# rbds_transmitter.net
KiCad netlist of a schematic drawn in EAGLE
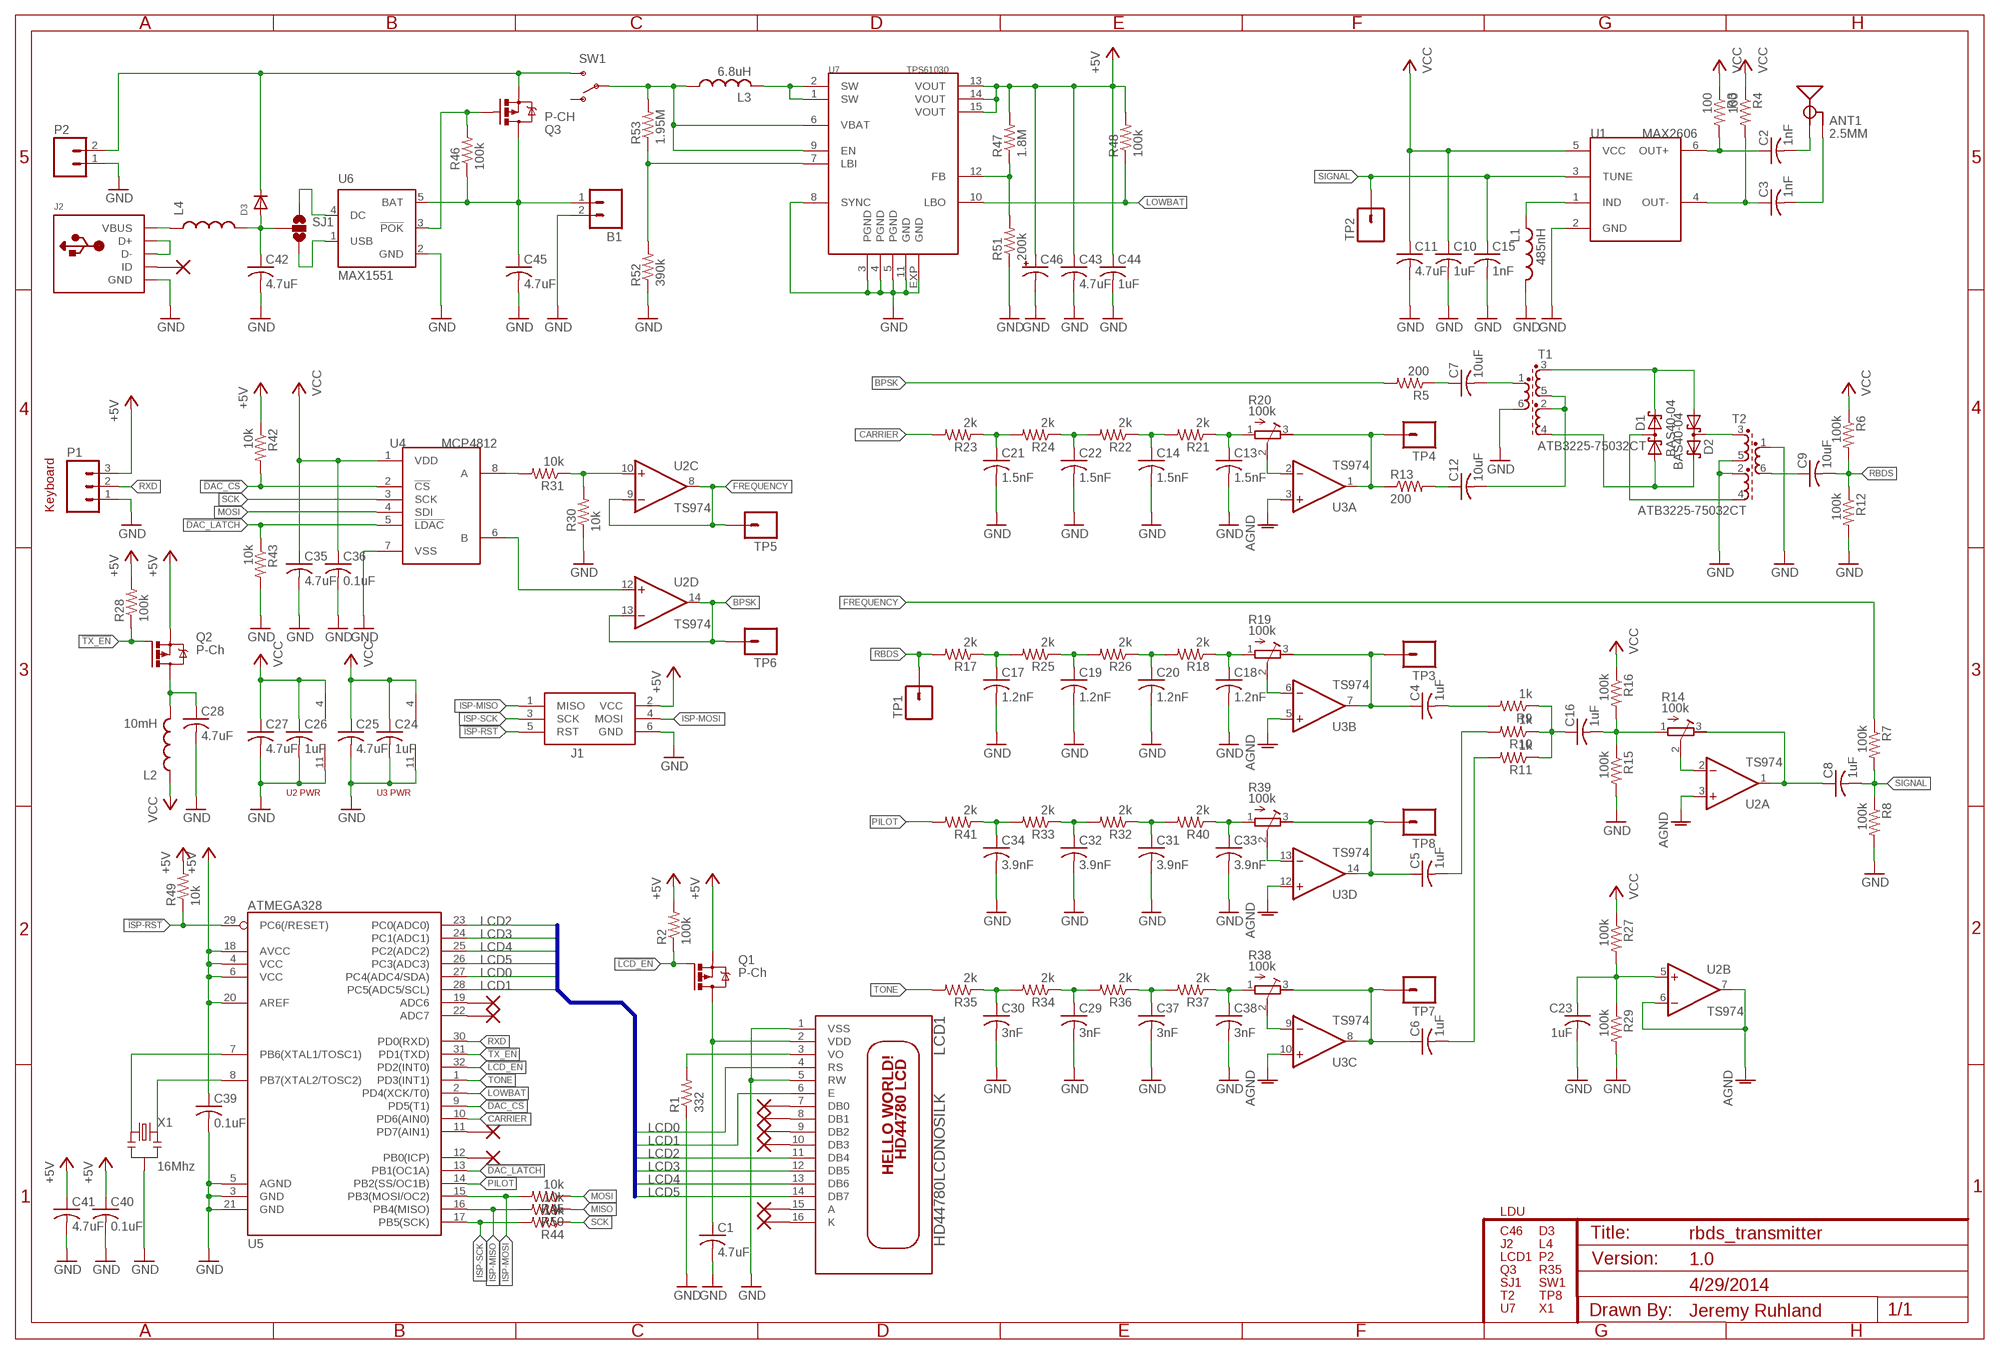
[diagram p0: schematic, sheet 1]

(export (version "E")
  (design (tool "Eeschema 10.0.6"))
  (components
    (comp (ref "ANT1")
      (value "2.5MM")
      (footprint "eagle-import:2.5MM_SCREW")
      (libsource (lib "eagle-import") (part "ANT2.5MM"))
    )
    (comp (ref "B1")
      (value "M02-JST-2MM-SMT")
      (footprint "eagle-import:JST-2-SMD")
      (libsource (lib "eagle-import") (part "M02-JST-2MM-SMT"))
    )
    (comp (ref "C1")
      (value "4.7uF")
      (footprint "eagle-import:C1206")
      (libsource (lib "eagle-import") (part "C-USC1206"))
    )
    (comp (ref "C2")
      (value "1nF")
      (footprint "eagle-import:C1206")
      (libsource (lib "eagle-import") (part "C-USC1206"))
    )
    (comp (ref "C3")
      (value "1nF")
      (footprint "eagle-import:C1206")
      (libsource (lib "eagle-import") (part "C-USC1206"))
    )
    (comp (ref "C4")
      (value "1uF")
      (footprint "eagle-import:C1206")
      (libsource (lib "eagle-import") (part "C-USC1206"))
    )
    (comp (ref "C5")
      (value "1uF")
      (footprint "eagle-import:C1206")
      (libsource (lib "eagle-import") (part "C-USC1206"))
    )
    (comp (ref "C6")
      (value "1uF")
      (footprint "eagle-import:C1206")
      (libsource (lib "eagle-import") (part "C-USC1206"))
    )
    (comp (ref "C7")
      (value "10uF")
      (footprint "eagle-import:C1206")
      (libsource (lib "eagle-import") (part "C-USC1206"))
    )
    (comp (ref "C8")
      (value "1uF")
      (footprint "eagle-import:C1206")
      (libsource (lib "eagle-import") (part "C-USC1206"))
    )
    (comp (ref "C9")
      (value "10uF")
      (footprint "eagle-import:C1206")
      (libsource (lib "eagle-import") (part "C-USC1206"))
    )
    (comp (ref "C10")
      (value "1uF")
      (footprint "eagle-import:C1206")
      (libsource (lib "eagle-import") (part "C-USC1206"))
    )
    (comp (ref "C11")
      (value "4.7uF")
      (footprint "eagle-import:C1206")
      (libsource (lib "eagle-import") (part "C-USC1206"))
    )
    (comp (ref "C12")
      (value "10uF")
      (footprint "eagle-import:C1206")
      (libsource (lib "eagle-import") (part "C-USC1206"))
    )
    (comp (ref "C13")
      (value "1.5nF")
      (footprint "eagle-import:C1206")
      (libsource (lib "eagle-import") (part "C-USC1206"))
    )
    (comp (ref "C14")
      (value "1.5nF")
      (footprint "eagle-import:C1206")
      (libsource (lib "eagle-import") (part "C-USC1206"))
    )
    (comp (ref "C15")
      (value "1nF")
      (footprint "eagle-import:C1206")
      (libsource (lib "eagle-import") (part "C-USC1206"))
    )
    (comp (ref "C16")
      (value "1uF")
      (footprint "eagle-import:C1206")
      (libsource (lib "eagle-import") (part "C-USC1206"))
    )
    (comp (ref "C17")
      (value "1.2nF")
      (footprint "eagle-import:C1206")
      (libsource (lib "eagle-import") (part "C-USC1206"))
    )
    (comp (ref "C18")
      (value "1.2nF")
      (footprint "eagle-import:C1206")
      (libsource (lib "eagle-import") (part "C-USC1206"))
    )
    (comp (ref "C19")
      (value "1.2nF")
      (footprint "eagle-import:C1206")
      (libsource (lib "eagle-import") (part "C-USC1206"))
    )
    (comp (ref "C20")
      (value "1.2nF")
      (footprint "eagle-import:C1206")
      (libsource (lib "eagle-import") (part "C-USC1206"))
    )
    (comp (ref "C21")
      (value "1.5nF")
      (footprint "eagle-import:C1206")
      (libsource (lib "eagle-import") (part "C-USC1206"))
    )
    (comp (ref "C22")
      (value "1.5nF")
      (footprint "eagle-import:C1206")
      (libsource (lib "eagle-import") (part "C-USC1206"))
    )
    (comp (ref "C23")
      (value "1uF")
      (footprint "eagle-import:C1206")
      (libsource (lib "eagle-import") (part "C-USC1206"))
    )
    (comp (ref "C24")
      (value "1uF")
      (footprint "eagle-import:C1206")
      (libsource (lib "eagle-import") (part "C-USC1206"))
    )
    (comp (ref "C25")
      (value "4.7uF")
      (footprint "eagle-import:C1206")
      (libsource (lib "eagle-import") (part "C-USC1206"))
    )
    (comp (ref "C26")
      (value "1uF")
      (footprint "eagle-import:C1206")
      (libsource (lib "eagle-import") (part "C-USC1206"))
    )
    (comp (ref "C27")
      (value "4.7uF")
      (footprint "eagle-import:C1206")
      (libsource (lib "eagle-import") (part "C-USC1206"))
    )
    (comp (ref "C28")
      (value "4.7uF")
      (footprint "eagle-import:C1206")
      (libsource (lib "eagle-import") (part "C-USC1206"))
    )
    (comp (ref "C29")
      (value "3nF")
      (footprint "eagle-import:C1206")
      (libsource (lib "eagle-import") (part "C-USC1206"))
    )
    (comp (ref "C30")
      (value "3nF")
      (footprint "eagle-import:C1206")
      (libsource (lib "eagle-import") (part "C-USC1206"))
    )
    (comp (ref "C31")
      (value "3.9nF")
      (footprint "eagle-import:C1206")
      (libsource (lib "eagle-import") (part "C-USC1206"))
    )
    (comp (ref "C32")
      (value "3.9nF")
      (footprint "eagle-import:C1206")
      (libsource (lib "eagle-import") (part "C-USC1206"))
    )
    (comp (ref "C33")
      (value "3.9nF")
      (footprint "eagle-import:C1206")
      (libsource (lib "eagle-import") (part "C-USC1206"))
    )
    (comp (ref "C34")
      (value "3.9nF")
      (footprint "eagle-import:C1206")
      (libsource (lib "eagle-import") (part "C-USC1206"))
    )
    (comp (ref "C35")
      (value "4.7uF")
      (footprint "eagle-import:C1206")
      (libsource (lib "eagle-import") (part "C-USC1206"))
    )
    (comp (ref "C36")
      (value "0.1uF")
      (footprint "eagle-import:C1206")
      (libsource (lib "eagle-import") (part "C-USC1206"))
    )
    (comp (ref "C37")
      (value "3nF")
      (footprint "eagle-import:C1206")
      (libsource (lib "eagle-import") (part "C-USC1206"))
    )
    (comp (ref "C38")
      (value "3nF")
      (footprint "eagle-import:C1206")
      (libsource (lib "eagle-import") (part "C-USC1206"))
    )
    (comp (ref "C39")
      (value "0.1uF")
      (footprint "eagle-import:C1206")
      (libsource (lib "eagle-import") (part "C-USC1206"))
    )
    (comp (ref "C40")
      (value "0.1uF")
      (footprint "eagle-import:C1206")
      (libsource (lib "eagle-import") (part "C-USC1206"))
    )
    (comp (ref "C41")
      (value "4.7uF")
      (footprint "eagle-import:C1206")
      (libsource (lib "eagle-import") (part "C-USC1206"))
    )
    (comp (ref "C42")
      (value "4.7uF")
      (footprint "eagle-import:C1206")
      (libsource (lib "eagle-import") (part "C-USC1206"))
    )
    (comp (ref "C43")
      (value "4.7uF")
      (footprint "eagle-import:C1206")
      (libsource (lib "eagle-import") (part "C-USC1206"))
    )
    (comp (ref "C44")
      (value "1uF")
      (footprint "eagle-import:C1206")
      (libsource (lib "eagle-import") (part "C-USC1206"))
    )
    (comp (ref "C45")
      (value "4.7uF")
      (footprint "eagle-import:C1206")
      (libsource (lib "eagle-import") (part "C-USC1206"))
    )
    (comp (ref "C46")
      (value "CPOL-USE")
      (footprint "eagle-import:PANASONIC_E")
      (libsource (lib "eagle-import") (part "CPOL-USE"))
    )
    (comp (ref "D1")
      (value "BAS40-04")
      (footprint "eagle-import:SOT23")
      (libsource (lib "eagle-import") (part "BAS40-04"))
    )
    (comp (ref "D2")
      (value "BAS40-04")
      (footprint "eagle-import:SOT23")
      (libsource (lib "eagle-import") (part "BAS40-04"))
    )
    (comp (ref "D3")
      (value "DIODESOD-123")
      (footprint "eagle-import:SOD-123")
      (libsource (lib "eagle-import") (part "DIODESOD-123"))
    )
    (comp (ref "J1")
      (value "AVRISP-6")
      (footprint "eagle-import:AVRISP")
      (libsource (lib "eagle-import") (part "AVRISP-6"))
    )
    (comp (ref "J2")
      (value "USBMINIB")
      (footprint "eagle-import:USB-MINIB")
      (libsource (lib "eagle-import") (part "USBMINIB"))
    )
    (comp (ref "L1")
      (value "485nH")
      (footprint "eagle-import:L3216C")
      (libsource (lib "eagle-import") (part "L-USL3216C"))
    )
    (comp (ref "L2")
      (value "10mH")
      (footprint "eagle-import:1210")
      (libsource (lib "eagle-import") (part "INDUCTOR1210"))
    )
    (comp (ref "L3")
      (value "6.8uH")
      (footprint "eagle-import:8040")
      (libsource (lib "eagle-import") (part "L"))
    )
    (comp (ref "L4")
      (value "INDUCTOR1210")
      (footprint "eagle-import:1210")
      (libsource (lib "eagle-import") (part "INDUCTOR1210"))
    )
    (comp (ref "LCD1")
      (value "HD44780LCDNOSILK")
      (footprint "eagle-import:LCD1602_NOSILK")
      (libsource (lib "eagle-import") (part "HD44780LCDNOSILK"))
    )
    (comp (ref "P1")
      (value "M03PTH")
      (footprint "eagle-import:1X03")
      (libsource (lib "eagle-import") (part "M03PTH"))
    )
    (comp (ref "P2")
      (value "M023.5MM")
      (footprint "eagle-import:SCREWTERMINAL-3.5MM-2")
      (libsource (lib "eagle-import") (part "M023.5MM"))
    )
    (comp (ref "Q1")
      (value "P-Ch")
      (footprint "eagle-import:MICRO3")
      (libsource (lib "eagle-import") (part "IRLML5203"))
    )
    (comp (ref "Q2")
      (value "P-Ch")
      (footprint "eagle-import:MICRO3")
      (libsource (lib "eagle-import") (part "IRLML5203"))
    )
    (comp (ref "Q3")
      (value "P-CH")
      (footprint "eagle-import:SOT23-3")
      (libsource (lib "eagle-import") (part "MOSFET-PCHANNELSMD"))
    )
    (comp (ref "R1")
      (value "332")
      (footprint "eagle-import:R1206")
      (libsource (lib "eagle-import") (part "R-US_R1206"))
    )
    (comp (ref "R2")
      (value "100k")
      (footprint "eagle-import:R1206")
      (libsource (lib "eagle-import") (part "R-US_R1206"))
    )
    (comp (ref "R3")
      (value "100")
      (footprint "eagle-import:R1206")
      (libsource (lib "eagle-import") (part "R-US_R1206"))
    )
    (comp (ref "R4")
      (value "100")
      (footprint "eagle-import:R1206")
      (libsource (lib "eagle-import") (part "R-US_R1206"))
    )
    (comp (ref "R5")
      (value "200")
      (footprint "eagle-import:R1206")
      (libsource (lib "eagle-import") (part "R-US_R1206"))
    )
    (comp (ref "R6")
      (value "100k")
      (footprint "eagle-import:R1206")
      (libsource (lib "eagle-import") (part "R-US_R1206"))
    )
    (comp (ref "R7")
      (value "100k")
      (footprint "eagle-import:R1206")
      (libsource (lib "eagle-import") (part "R-US_R1206"))
    )
    (comp (ref "R8")
      (value "100k")
      (footprint "eagle-import:R1206")
      (libsource (lib "eagle-import") (part "R-US_R1206"))
    )
    (comp (ref "R9")
      (value "1k")
      (footprint "eagle-import:R1206")
      (libsource (lib "eagle-import") (part "R-US_R1206"))
    )
    (comp (ref "R10")
      (value "1k")
      (footprint "eagle-import:R1206")
      (libsource (lib "eagle-import") (part "R-US_R1206"))
    )
    (comp (ref "R11")
      (value "1k")
      (footprint "eagle-import:R1206")
      (libsource (lib "eagle-import") (part "R-US_R1206"))
    )
    (comp (ref "R12")
      (value "100k")
      (footprint "eagle-import:R1206")
      (libsource (lib "eagle-import") (part "R-US_R1206"))
    )
    (comp (ref "R13")
      (value "200")
      (footprint "eagle-import:R1206")
      (libsource (lib "eagle-import") (part "R-US_R1206"))
    )
    (comp (ref "R14")
      (value "100k")
      (footprint "eagle-import:RTRIM3304W")
      (libsource (lib "eagle-import") (part "R-TRIMM3304W"))
    )
    (comp (ref "R15")
      (value "100k")
      (footprint "eagle-import:R1206")
      (libsource (lib "eagle-import") (part "R-US_R1206"))
    )
    (comp (ref "R16")
      (value "100k")
      (footprint "eagle-import:R1206")
      (libsource (lib "eagle-import") (part "R-US_R1206"))
    )
    (comp (ref "R17")
      (value "2k")
      (footprint "eagle-import:R1206")
      (libsource (lib "eagle-import") (part "R-US_R1206"))
    )
    (comp (ref "R18")
      (value "2k")
      (footprint "eagle-import:R1206")
      (libsource (lib "eagle-import") (part "R-US_R1206"))
    )
    (comp (ref "R19")
      (value "100k")
      (footprint "eagle-import:RTRIM3304W")
      (libsource (lib "eagle-import") (part "R-TRIMM3304W"))
    )
    (comp (ref "R20")
      (value "100k")
      (footprint "eagle-import:RTRIM3304W")
      (libsource (lib "eagle-import") (part "R-TRIMM3304W"))
    )
    (comp (ref "R21")
      (value "2k")
      (footprint "eagle-import:R1206")
      (libsource (lib "eagle-import") (part "R-US_R1206"))
    )
    (comp (ref "R22")
      (value "2k")
      (footprint "eagle-import:R1206")
      (libsource (lib "eagle-import") (part "R-US_R1206"))
    )
    (comp (ref "R23")
      (value "2k")
      (footprint "eagle-import:R1206")
      (libsource (lib "eagle-import") (part "R-US_R1206"))
    )
    (comp (ref "R24")
      (value "2k")
      (footprint "eagle-import:R1206")
      (libsource (lib "eagle-import") (part "R-US_R1206"))
    )
    (comp (ref "R25")
      (value "2k")
      (footprint "eagle-import:R1206")
      (libsource (lib "eagle-import") (part "R-US_R1206"))
    )
    (comp (ref "R26")
      (value "2k")
      (footprint "eagle-import:R1206")
      (libsource (lib "eagle-import") (part "R-US_R1206"))
    )
    (comp (ref "R27")
      (value "100k")
      (footprint "eagle-import:R1206")
      (libsource (lib "eagle-import") (part "R-US_R1206"))
    )
    (comp (ref "R28")
      (value "100k")
      (footprint "eagle-import:R1206")
      (libsource (lib "eagle-import") (part "R-US_R1206"))
    )
    (comp (ref "R29")
      (value "100k")
      (footprint "eagle-import:R1206")
      (libsource (lib "eagle-import") (part "R-US_R1206"))
    )
    (comp (ref "R30")
      (value "10k")
      (footprint "eagle-import:R1206")
      (libsource (lib "eagle-import") (part "R-US_R1206"))
    )
    (comp (ref "R31")
      (value "10k")
      (footprint "eagle-import:R1206")
      (libsource (lib "eagle-import") (part "R-US_R1206"))
    )
    (comp (ref "R32")
      (value "2k")
      (footprint "eagle-import:R1206")
      (libsource (lib "eagle-import") (part "R-US_R1206"))
    )
    (comp (ref "R33")
      (value "2k")
      (footprint "eagle-import:R1206")
      (libsource (lib "eagle-import") (part "R-US_R1206"))
    )
    (comp (ref "R34")
      (value "2k")
      (footprint "eagle-import:R1206")
      (libsource (lib "eagle-import") (part "R-US_R1206"))
    )
    (comp (ref "R35")
      (value "2k")
      (footprint "eagle-import:R1206")
      (libsource (lib "eagle-import") (part "R-US_R1206"))
    )
    (comp (ref "R36")
      (value "2k")
      (footprint "eagle-import:R1206")
      (libsource (lib "eagle-import") (part "R-US_R1206"))
    )
    (comp (ref "R37")
      (value "2k")
      (footprint "eagle-import:R1206")
      (libsource (lib "eagle-import") (part "R-US_R1206"))
    )
    (comp (ref "R38")
      (value "100k")
      (footprint "eagle-import:RTRIM3304W")
      (libsource (lib "eagle-import") (part "R-TRIMM3304W"))
    )
    (comp (ref "R39")
      (value "100k")
      (footprint "eagle-import:RTRIM3304W")
      (libsource (lib "eagle-import") (part "R-TRIMM3304W"))
    )
    (comp (ref "R40")
      (value "2k")
      (footprint "eagle-import:R1206")
      (libsource (lib "eagle-import") (part "R-US_R1206"))
    )
    (comp (ref "R41")
      (value "2k")
      (footprint "eagle-import:R1206")
      (libsource (lib "eagle-import") (part "R-US_R1206"))
    )
    (comp (ref "R42")
      (value "10k")
      (footprint "eagle-import:R1206")
      (libsource (lib "eagle-import") (part "R-US_R1206"))
    )
    (comp (ref "R43")
      (value "10k")
      (footprint "eagle-import:R1206")
      (libsource (lib "eagle-import") (part "R-US_R1206"))
    )
    (comp (ref "R44")
      (value "10k")
      (footprint "eagle-import:R1206")
      (libsource (lib "eagle-import") (part "R-US_R1206"))
    )
    (comp (ref "R45")
      (value "10k")
      (footprint "eagle-import:R1206")
      (libsource (lib "eagle-import") (part "R-US_R1206"))
    )
    (comp (ref "R46")
      (value "100k")
      (footprint "eagle-import:R1206")
      (libsource (lib "eagle-import") (part "R-US_R1206"))
    )
    (comp (ref "R47")
      (value "1.8M")
      (footprint "eagle-import:R1206")
      (libsource (lib "eagle-import") (part "R-US_R1206"))
    )
    (comp (ref "R48")
      (value "100k")
      (footprint "eagle-import:R1206")
      (libsource (lib "eagle-import") (part "R-US_R1206"))
    )
    (comp (ref "R49")
      (value "10k")
      (footprint "eagle-import:R1206")
      (libsource (lib "eagle-import") (part "R-US_R1206"))
    )
    (comp (ref "R50")
      (value "10k")
      (footprint "eagle-import:R1206")
      (libsource (lib "eagle-import") (part "R-US_R1206"))
    )
    (comp (ref "R51")
      (value "200k")
      (footprint "eagle-import:R1206")
      (libsource (lib "eagle-import") (part "R-US_R1206"))
    )
    (comp (ref "R52")
      (value "390k")
      (footprint "eagle-import:R1206")
      (libsource (lib "eagle-import") (part "R-US_R1206"))
    )
    (comp (ref "R53")
      (value "1.95M")
      (footprint "eagle-import:R1206")
      (libsource (lib "eagle-import") (part "R-US_R1206"))
    )
    (comp (ref "SJ1")
      (value "SOLDERJUMPER_2WAYS")
      (footprint "eagle-import:SJ_3")
      (libsource (lib "eagle-import") (part "SOLDERJUMPER_2WAYS"))
    )
    (comp (ref "SW1")
      (value "SWITCH-SPSTSMD2")
      (footprint "eagle-import:SWITCH-SPDT-SMD")
      (libsource (lib "eagle-import") (part "SWITCH-SPSTSMD2"))
    )
    (comp (ref "T1")
      (value "ATB3225-75032CT")
      (footprint "eagle-import:TRANS")
      (libsource (lib "eagle-import") (part "ATB3225-75032CT"))
    )
    (comp (ref "T2")
      (value "ATB3225-75032CT")
      (footprint "eagle-import:TRANS")
      (libsource (lib "eagle-import") (part "ATB3225-75032CT"))
    )
    (comp (ref "TP1")
      (value "M01PTH")
      (footprint "eagle-import:1X01")
      (libsource (lib "eagle-import") (part "M01PTH"))
    )
    (comp (ref "TP2")
      (value "M01PTH")
      (footprint "eagle-import:1X01")
      (libsource (lib "eagle-import") (part "M01PTH"))
    )
    (comp (ref "TP3")
      (value "M01PTH")
      (footprint "eagle-import:1X01")
      (libsource (lib "eagle-import") (part "M01PTH"))
    )
    (comp (ref "TP4")
      (value "M01PTH")
      (footprint "eagle-import:1X01")
      (libsource (lib "eagle-import") (part "M01PTH"))
    )
    (comp (ref "TP5")
      (value "M01PTH")
      (footprint "eagle-import:1X01")
      (libsource (lib "eagle-import") (part "M01PTH"))
    )
    (comp (ref "TP6")
      (value "M01PTH")
      (footprint "eagle-import:1X01")
      (libsource (lib "eagle-import") (part "M01PTH"))
    )
    (comp (ref "TP7")
      (value "M01PTH")
      (footprint "eagle-import:1X01")
      (libsource (lib "eagle-import") (part "M01PTH"))
    )
    (comp (ref "TP8")
      (value "M01PTH")
      (footprint "eagle-import:1X01")
      (libsource (lib "eagle-import") (part "M01PTH"))
    )
    (comp (ref "U1")
      (value "MAX2606")
      (footprint "eagle-import:SOT23-6L")
      (libsource (lib "eagle-import") (part "MAX2606"))
    )
    (comp (ref "U2")
      (value "TS974")
      (footprint "eagle-import:SO14")
      (libsource (lib "eagle-import") (part "OPA4743UA"))
    )
    (comp (ref "U3")
      (value "TS974")
      (footprint "eagle-import:SO14")
      (libsource (lib "eagle-import") (part "OPA4743UA"))
    )
    (comp (ref "U4")
      (value "MCP4812")
      (footprint "eagle-import:SO-08")
      (libsource (lib "eagle-import") (part "MCP4812"))
    )
    (comp (ref "U5")
      (value "ATMEGA328")
      (footprint "eagle-import:TQFP32-08")
      (libsource (lib "eagle-import") (part "ATMEGA168"))
    )
    (comp (ref "U6")
      (value "MAX1551")
      (footprint "eagle-import:SOT23-5L")
      (fields (field (name "MF") "MAXIM") (field (name "MPN") "MAX1551EZK-T"))
      (libsource (lib "eagle-import") (part "MAX1551"))
    )
    (comp (ref "U7")
      (value "TPS61030")
      (footprint "eagle-import:HTSSOP16")
      (libsource (lib "eagle-import") (part "TPS61030"))
    )
    (comp (ref "X1")
      (value "16Mhz")
      (footprint "eagle-import:RESONATOR-SMD")
      (libsource (lib "eagle-import") (part "RESONATORSMD"))
    )
  )
  (nets
    (net (code "1") (name "+5V") (class "Default")
      (node (ref "C39") (pin "1") (pinfunction "1_1") (pintype "passive"))
      (node (ref "C40") (pin "1") (pinfunction "1_1") (pintype "passive"))
      (node (ref "C41") (pin "1") (pinfunction "1_1") (pintype "passive"))
      (node (ref "C43") (pin "1") (pinfunction "1_1") (pintype "passive"))
      (node (ref "C44") (pin "1") (pinfunction "1_1") (pintype "passive"))
      (node (ref "C46") (pin "+") (pinfunction "+_+") (pintype "passive"))
      (node (ref "J1") (pin "2") (pinfunction "VCC_2") (pintype "power_in"))
      (node (ref "P1") (pin "3") (pinfunction "3_3") (pintype "passive"))
      (node (ref "Q1") (pin "2") (pinfunction "S_2") (pintype "passive"))
      (node (ref "Q2") (pin "2") (pinfunction "S_2") (pintype "passive"))
      (node (ref "R2") (pin "2") (pinfunction "2_2") (pintype "passive"))
      (node (ref "R28") (pin "2") (pinfunction "2_2") (pintype "passive"))
      (node (ref "R42") (pin "1") (pinfunction "1_1") (pintype "passive"))
      (node (ref "R47") (pin "2") (pinfunction "2_2") (pintype "passive"))
      (node (ref "R48") (pin "2") (pinfunction "2_2") (pintype "passive"))
      (node (ref "R49") (pin "2") (pinfunction "2_2") (pintype "passive"))
      (node (ref "U5") (pin "18") (pinfunction "AVCC_18") (pintype "bidirectional"))
      (node (ref "U5") (pin "20") (pinfunction "AREF_20") (pintype "bidirectional"))
      (node (ref "U5") (pin "4") (pinfunction "VCC_4") (pintype "bidirectional"))
      (node (ref "U5") (pin "6") (pinfunction "VCC_6") (pintype "bidirectional"))
      (node (ref "U7") (pin "13") (pinfunction "VOUT_13") (pintype "bidirectional"))
      (node (ref "U7") (pin "14") (pinfunction "VOUT_14") (pintype "bidirectional"))
      (node (ref "U7") (pin "15") (pinfunction "VOUT_15") (pintype "bidirectional"))
    )
    (net (code "2") (name "/LCD0") (class "Default")
      (node (ref "LCD1") (pin "4") (pinfunction "RS_4") (pintype "input"))
      (node (ref "U5") (pin "27") (pinfunction "PC4(ADC4/SDA)_27") (pintype "bidirectional"))
    )
    (net (code "3") (name "/LCD1") (class "Default")
      (node (ref "LCD1") (pin "6") (pinfunction "E_6") (pintype "input"))
      (node (ref "U5") (pin "28") (pinfunction "PC5(ADC5/SCL)_28") (pintype "bidirectional"))
    )
    (net (code "4") (name "/LCD2") (class "Default")
      (node (ref "LCD1") (pin "11") (pinfunction "DB4_11") (pintype "bidirectional"))
      (node (ref "U5") (pin "23") (pinfunction "PC0(ADC0)_23") (pintype "bidirectional"))
    )
    (net (code "5") (name "/LCD3") (class "Default")
      (node (ref "LCD1") (pin "12") (pinfunction "DB5_12") (pintype "bidirectional"))
      (node (ref "U5") (pin "24") (pinfunction "PC1(ADC1)_24") (pintype "bidirectional"))
    )
    (net (code "6") (name "/LCD4") (class "Default")
      (node (ref "LCD1") (pin "13") (pinfunction "DB6_13") (pintype "bidirectional"))
      (node (ref "U5") (pin "25") (pinfunction "PC2(ADC2)_25") (pintype "bidirectional"))
    )
    (net (code "7") (name "/LCD5") (class "Default")
      (node (ref "LCD1") (pin "14") (pinfunction "DB7_14") (pintype "bidirectional"))
      (node (ref "U5") (pin "26") (pinfunction "PC3(ADC3)_26") (pintype "bidirectional"))
    )
    (net (code "8") (name "/~{DAC_CS}") (class "Default")
      (node (ref "R42") (pin "2") (pinfunction "2_2") (pintype "passive"))
      (node (ref "U4") (pin "2") (pinfunction "~{CS}_2") (pintype "bidirectional"))
      (node (ref "U5") (pin "9") (pinfunction "PD5(T1)_9") (pintype "bidirectional"))
    )
    (net (code "9") (name "/~{DAC_LATCH}") (class "Default")
      (node (ref "R43") (pin "1") (pinfunction "1_1") (pintype "passive"))
      (node (ref "U4") (pin "5") (pinfunction "~{LDAC}_5") (pintype "bidirectional"))
      (node (ref "U5") (pin "13") (pinfunction "PB1(OC1A)_13") (pintype "bidirectional"))
    )
    (net (code "10") (name "/~{ISP-RST}") (class "Default")
      (node (ref "J1") (pin "5") (pinfunction "RST_5") (pintype "output"))
      (node (ref "R49") (pin "1") (pinfunction "1_1") (pintype "passive"))
      (node (ref "U5") (pin "29") (pinfunction "PC6(/RESET)_29") (pintype "bidirectional"))
    )
    (net (code "11") (name "/~{LCD_EN}") (class "Default")
      (node (ref "Q1") (pin "1") (pinfunction "G_1") (pintype "passive"))
      (node (ref "R2") (pin "1") (pinfunction "1_1") (pintype "passive"))
      (node (ref "U5") (pin "32") (pinfunction "PD2(INT0)_32") (pintype "bidirectional"))
    )
    (net (code "12") (name "/~{TX_EN}") (class "Default")
      (node (ref "Q2") (pin "1") (pinfunction "G_1") (pintype "passive"))
      (node (ref "R28") (pin "1") (pinfunction "1_1") (pintype "passive"))
      (node (ref "U5") (pin "31") (pinfunction "PD1(TXD)_31") (pintype "bidirectional"))
    )
    (net (code "13") (name "AGND") (class "Default")
      (node (ref "U2") (pin "3") (pinfunction "+IN_3") (pintype "input"))
      (node (ref "U2") (pin "6") (pinfunction "-IN_6") (pintype "input"))
      (node (ref "U2") (pin "7") (pinfunction "OUT_7") (pintype "output"))
      (node (ref "U3") (pin "10") (pinfunction "+IN_10") (pintype "input"))
      (node (ref "U3") (pin "12") (pinfunction "+IN_12") (pintype "input"))
      (node (ref "U3") (pin "3") (pinfunction "+IN_3") (pintype "input"))
      (node (ref "U3") (pin "5") (pinfunction "+IN_5") (pintype "input"))
    )
    (net (code "14") (name "BPSK") (class "Default")
      (node (ref "R5") (pin "2") (pinfunction "2_2") (pintype "passive"))
      (node (ref "TP6") (pin "1") (pinfunction "1_1") (pintype "passive"))
      (node (ref "U2") (pin "13") (pinfunction "-IN_13") (pintype "input"))
      (node (ref "U2") (pin "14") (pinfunction "OUT_14") (pintype "output"))
    )
    (net (code "15") (name "CARRIER") (class "Default")
      (node (ref "R23") (pin "2") (pinfunction "2_2") (pintype "passive"))
      (node (ref "U5") (pin "10") (pinfunction "PD6(AIN0)_10") (pintype "bidirectional"))
    )
    (net (code "16") (name "FREQUENCY") (class "Default")
      (node (ref "R7") (pin "1") (pinfunction "1_1") (pintype "passive"))
      (node (ref "TP5") (pin "1") (pinfunction "1_1") (pintype "passive"))
      (node (ref "U2") (pin "8") (pinfunction "OUT_8") (pintype "output"))
      (node (ref "U2") (pin "9") (pinfunction "-IN_9") (pintype "input"))
    )
    (net (code "17") (name "GND") (class "Default")
      (node (ref "B1") (pin "2") (pinfunction "2_2") (pintype "passive"))
      (node (ref "C1") (pin "2") (pinfunction "2_2") (pintype "passive"))
      (node (ref "C10") (pin "2") (pinfunction "2_2") (pintype "passive"))
      (node (ref "C11") (pin "2") (pinfunction "2_2") (pintype "passive"))
      (node (ref "C13") (pin "2") (pinfunction "2_2") (pintype "passive"))
      (node (ref "C14") (pin "2") (pinfunction "2_2") (pintype "passive"))
      (node (ref "C15") (pin "2") (pinfunction "2_2") (pintype "passive"))
      (node (ref "C17") (pin "2") (pinfunction "2_2") (pintype "passive"))
      (node (ref "C18") (pin "2") (pinfunction "2_2") (pintype "passive"))
      (node (ref "C19") (pin "2") (pinfunction "2_2") (pintype "passive"))
      (node (ref "C20") (pin "2") (pinfunction "2_2") (pintype "passive"))
      (node (ref "C21") (pin "2") (pinfunction "2_2") (pintype "passive"))
      (node (ref "C22") (pin "2") (pinfunction "2_2") (pintype "passive"))
      (node (ref "C23") (pin "2") (pinfunction "2_2") (pintype "passive"))
      (node (ref "C24") (pin "2") (pinfunction "2_2") (pintype "passive"))
      (node (ref "C25") (pin "2") (pinfunction "2_2") (pintype "passive"))
      (node (ref "C26") (pin "2") (pinfunction "2_2") (pintype "passive"))
      (node (ref "C27") (pin "2") (pinfunction "2_2") (pintype "passive"))
      (node (ref "C28") (pin "2") (pinfunction "2_2") (pintype "passive"))
      (node (ref "C29") (pin "2") (pinfunction "2_2") (pintype "passive"))
      (node (ref "C30") (pin "2") (pinfunction "2_2") (pintype "passive"))
      (node (ref "C31") (pin "2") (pinfunction "2_2") (pintype "passive"))
      (node (ref "C32") (pin "2") (pinfunction "2_2") (pintype "passive"))
      (node (ref "C33") (pin "2") (pinfunction "2_2") (pintype "passive"))
      (node (ref "C34") (pin "2") (pinfunction "2_2") (pintype "passive"))
      (node (ref "C35") (pin "2") (pinfunction "2_2") (pintype "passive"))
      (node (ref "C36") (pin "2") (pinfunction "2_2") (pintype "passive"))
      (node (ref "C37") (pin "2") (pinfunction "2_2") (pintype "passive"))
      (node (ref "C38") (pin "2") (pinfunction "2_2") (pintype "passive"))
      (node (ref "C39") (pin "2") (pinfunction "2_2") (pintype "passive"))
      (node (ref "C40") (pin "2") (pinfunction "2_2") (pintype "passive"))
      (node (ref "C41") (pin "2") (pinfunction "2_2") (pintype "passive"))
      (node (ref "C42") (pin "2") (pinfunction "2_2") (pintype "passive"))
      (node (ref "C43") (pin "2") (pinfunction "2_2") (pintype "passive"))
      (node (ref "C44") (pin "2") (pinfunction "2_2") (pintype "passive"))
      (node (ref "C45") (pin "2") (pinfunction "2_2") (pintype "passive"))
      (node (ref "C46") (pin "-") (pinfunction "-_-") (pintype "passive"))
      (node (ref "J1") (pin "6") (pinfunction "GND_6") (pintype "power_in"))
      (node (ref "J2") (pin "GND") (pinfunction "GND_GND") (pintype "power_in"))
      (node (ref "L1") (pin "1") (pinfunction "1_1") (pintype "passive"))
      (node (ref "LCD1") (pin "1") (pinfunction "VSS_1") (pintype "power_in"))
      (node (ref "LCD1") (pin "5") (pinfunction "RW_5") (pintype "input"))
      (node (ref "P1") (pin "1") (pinfunction "1_1") (pintype "passive"))
      (node (ref "P2") (pin "1") (pinfunction "1_1") (pintype "passive"))
      (node (ref "R1") (pin "1") (pinfunction "1_1") (pintype "passive"))
      (node (ref "R12") (pin "2") (pinfunction "2_2") (pintype "passive"))
      (node (ref "R15") (pin "2") (pinfunction "2_2") (pintype "passive"))
      (node (ref "R29") (pin "2") (pinfunction "2_2") (pintype "passive"))
      (node (ref "R30") (pin "1") (pinfunction "1_1") (pintype "passive"))
      (node (ref "R43") (pin "2") (pinfunction "2_2") (pintype "passive"))
      (node (ref "R51") (pin "1") (pinfunction "1_1") (pintype "passive"))
      (node (ref "R52") (pin "1") (pinfunction "1_1") (pintype "passive"))
      (node (ref "R8") (pin "2") (pinfunction "2_2") (pintype "passive"))
      (node (ref "T1") (pin "6") (pinfunction "6_6") (pintype "passive"))
      (node (ref "T2") (pin "1") (pinfunction "1_1") (pintype "passive"))
      (node (ref "T2") (pin "2") (pinfunction "2_2") (pintype "passive"))
      (node (ref "T2") (pin "5") (pinfunction "5_5") (pintype "passive"))
      (node (ref "U1") (pin "2") (pinfunction "GND_2") (pintype "bidirectional"))
      (node (ref "U2") (pin "11") (pinfunction "V-_11") (pintype "power_in"))
      (node (ref "U3") (pin "11") (pinfunction "V-_11") (pintype "power_in"))
      (node (ref "U4") (pin "7") (pinfunction "VSS_7") (pintype "bidirectional"))
      (node (ref "U5") (pin "21") (pinfunction "GND_21") (pintype "bidirectional"))
      (node (ref "U5") (pin "3") (pinfunction "GND_3") (pintype "bidirectional"))
      (node (ref "U5") (pin "5") (pinfunction "AGND_5") (pintype "bidirectional"))
      (node (ref "U6") (pin "2") (pinfunction "GND_2") (pintype "power_in"))
      (node (ref "U7") (pin "11") (pinfunction "GND_11") (pintype "bidirectional"))
      (node (ref "U7") (pin "3") (pinfunction "PGND_3") (pintype "bidirectional"))
      (node (ref "U7") (pin "4") (pinfunction "PGND_4") (pintype "bidirectional"))
      (node (ref "U7") (pin "5") (pinfunction "PGND_5") (pintype "bidirectional"))
      (node (ref "U7") (pin "8") (pinfunction "SYNC_8") (pintype "bidirectional"))
      (node (ref "U7") (pin "EXP") (pinfunction "GND_EXP") (pintype "bidirectional"))
      (node (ref "X1") (pin "2") (pinfunction "2_2") (pintype "passive"))
    )
    (net (code "18") (name "ISP-MISO") (class "Default")
      (node (ref "J1") (pin "1") (pinfunction "MISO_1") (pintype "input"))
      (node (ref "R50") (pin "2") (pinfunction "2_2") (pintype "passive"))
      (node (ref "U5") (pin "16") (pinfunction "PB4(MISO)_16") (pintype "bidirectional"))
    )
    (net (code "19") (name "ISP-MOSI") (class "Default")
      (node (ref "J1") (pin "4") (pinfunction "MOSI_4") (pintype "output"))
      (node (ref "R45") (pin "2") (pinfunction "2_2") (pintype "passive"))
      (node (ref "U5") (pin "15") (pinfunction "PB3(MOSI/OC2)_15") (pintype "bidirectional"))
    )
    (net (code "20") (name "ISP-SCK") (class "Default")
      (node (ref "J1") (pin "3") (pinfunction "SCK_3") (pintype "output"))
      (node (ref "R44") (pin "2") (pinfunction "2_2") (pintype "passive"))
      (node (ref "U5") (pin "17") (pinfunction "PB5(SCK)_17") (pintype "bidirectional"))
    )
    (net (code "21") (name "LOWBAT") (class "Default")
      (node (ref "R48") (pin "1") (pinfunction "1_1") (pintype "passive"))
      (node (ref "U5") (pin "2") (pinfunction "PD4(XCK/T0)_2") (pintype "bidirectional"))
      (node (ref "U7") (pin "10") (pinfunction "LBO_10") (pintype "bidirectional"))
    )
    (net (code "22") (name "MISO") (class "Default")
      (node (ref "R50") (pin "1") (pinfunction "1_1") (pintype "passive"))
    )
    (net (code "23") (name "MOSI") (class "Default")
      (node (ref "R45") (pin "1") (pinfunction "1_1") (pintype "passive"))
      (node (ref "U4") (pin "4") (pinfunction "SDI_4") (pintype "bidirectional"))
    )
    (net (code "24") (name "Net-(ANT1-GND)") (class "Default")
      (node (ref "ANT1") (pin "1") (pinfunction "GND_1") (pintype "bidirectional"))
      (node (ref "C3") (pin "2") (pinfunction "2_2") (pintype "passive"))
    )
    (net (code "25") (name "Net-(ANT1-SIGNAL)") (class "Default")
      (node (ref "ANT1") (pin "2") (pinfunction "SIGNAL_2") (pintype "bidirectional"))
      (node (ref "C2") (pin "2") (pinfunction "2_2") (pintype "passive"))
    )
    (net (code "26") (name "Net-(C4-Pad2)") (class "Default")
      (node (ref "C4") (pin "2") (pinfunction "2_2") (pintype "passive"))
      (node (ref "R9") (pin "2") (pinfunction "2_2") (pintype "passive"))
    )
    (net (code "27") (name "Net-(C5-Pad2)") (class "Default")
      (node (ref "C5") (pin "2") (pinfunction "2_2") (pintype "passive"))
      (node (ref "R10") (pin "2") (pinfunction "2_2") (pintype "passive"))
    )
    (net (code "28") (name "Net-(C6-Pad2)") (class "Default")
      (node (ref "C6") (pin "2") (pinfunction "2_2") (pintype "passive"))
      (node (ref "R11") (pin "2") (pinfunction "2_2") (pintype "passive"))
    )
    (net (code "29") (name "Net-(C7-Pad1)") (class "Default")
      (node (ref "C7") (pin "1") (pinfunction "1_1") (pintype "passive"))
      (node (ref "R5") (pin "1") (pinfunction "1_1") (pintype "passive"))
    )
    (net (code "30") (name "Net-(C7-Pad2)") (class "Default")
      (node (ref "C7") (pin "2") (pinfunction "2_2") (pintype "passive"))
      (node (ref "T1") (pin "1") (pinfunction "1_1") (pintype "passive"))
    )
    (net (code "31") (name "Net-(C9-Pad1)") (class "Default")
      (node (ref "C9") (pin "1") (pinfunction "1_1") (pintype "passive"))
      (node (ref "T2") (pin "6") (pinfunction "6_6") (pintype "passive"))
    )
    (net (code "32") (name "Net-(C12-Pad1)") (class "Default")
      (node (ref "C12") (pin "1") (pinfunction "1_1") (pintype "passive"))
      (node (ref "R13") (pin "2") (pinfunction "2_2") (pintype "passive"))
    )
    (net (code "33") (name "Net-(C12-Pad2)") (class "Default")
      (node (ref "C12") (pin "2") (pinfunction "2_2") (pintype "passive"))
      (node (ref "T1") (pin "2") (pinfunction "2_2") (pintype "passive"))
      (node (ref "T1") (pin "5") (pinfunction "5_5") (pintype "passive"))
    )
    (net (code "34") (name "Net-(C14-Pad1)") (class "Default")
      (node (ref "C14") (pin "1") (pinfunction "1_1") (pintype "passive"))
      (node (ref "R21") (pin "2") (pinfunction "2_2") (pintype "passive"))
      (node (ref "R22") (pin "1") (pinfunction "1_1") (pintype "passive"))
    )
    (net (code "35") (name "Net-(C16-Pad1)") (class "Default")
      (node (ref "C16") (pin "1") (pinfunction "1_1") (pintype "passive"))
      (node (ref "R10") (pin "1") (pinfunction "1_1") (pintype "passive"))
      (node (ref "R11") (pin "1") (pinfunction "1_1") (pintype "passive"))
      (node (ref "R9") (pin "1") (pinfunction "1_1") (pintype "passive"))
    )
    (net (code "36") (name "Net-(C17-Pad1)") (class "Default")
      (node (ref "C17") (pin "1") (pinfunction "1_1") (pintype "passive"))
      (node (ref "R17") (pin "1") (pinfunction "1_1") (pintype "passive"))
      (node (ref "R25") (pin "2") (pinfunction "2_2") (pintype "passive"))
    )
    (net (code "37") (name "Net-(C19-Pad1)") (class "Default")
      (node (ref "C19") (pin "1") (pinfunction "1_1") (pintype "passive"))
      (node (ref "R25") (pin "1") (pinfunction "1_1") (pintype "passive"))
      (node (ref "R26") (pin "2") (pinfunction "2_2") (pintype "passive"))
    )
    (net (code "38") (name "Net-(C20-Pad1)") (class "Default")
      (node (ref "C20") (pin "1") (pinfunction "1_1") (pintype "passive"))
      (node (ref "R18") (pin "2") (pinfunction "2_2") (pintype "passive"))
      (node (ref "R26") (pin "1") (pinfunction "1_1") (pintype "passive"))
    )
    (net (code "39") (name "Net-(C21-Pad1)") (class "Default")
      (node (ref "C21") (pin "1") (pinfunction "1_1") (pintype "passive"))
      (node (ref "R23") (pin "1") (pinfunction "1_1") (pintype "passive"))
      (node (ref "R24") (pin "2") (pinfunction "2_2") (pintype "passive"))
    )
    (net (code "40") (name "Net-(C22-Pad1)") (class "Default")
      (node (ref "C22") (pin "1") (pinfunction "1_1") (pintype "passive"))
      (node (ref "R22") (pin "2") (pinfunction "2_2") (pintype "passive"))
      (node (ref "R24") (pin "1") (pinfunction "1_1") (pintype "passive"))
    )
    (net (code "41") (name "Net-(C29-Pad1)") (class "Default")
      (node (ref "C29") (pin "1") (pinfunction "1_1") (pintype "passive"))
      (node (ref "R34") (pin "1") (pinfunction "1_1") (pintype "passive"))
      (node (ref "R36") (pin "2") (pinfunction "2_2") (pintype "passive"))
    )
    (net (code "42") (name "Net-(C30-Pad1)") (class "Default")
      (node (ref "C30") (pin "1") (pinfunction "1_1") (pintype "passive"))
      (node (ref "R34") (pin "2") (pinfunction "2_2") (pintype "passive"))
      (node (ref "R35") (pin "1") (pinfunction "1_1") (pintype "passive"))
    )
    (net (code "43") (name "Net-(C31-Pad1)") (class "Default")
      (node (ref "C31") (pin "1") (pinfunction "1_1") (pintype "passive"))
      (node (ref "R32") (pin "1") (pinfunction "1_1") (pintype "passive"))
      (node (ref "R40") (pin "2") (pinfunction "2_2") (pintype "passive"))
    )
    (net (code "44") (name "Net-(C32-Pad1)") (class "Default")
      (node (ref "C32") (pin "1") (pinfunction "1_1") (pintype "passive"))
      (node (ref "R32") (pin "2") (pinfunction "2_2") (pintype "passive"))
      (node (ref "R33") (pin "1") (pinfunction "1_1") (pintype "passive"))
    )
    (net (code "45") (name "Net-(C34-Pad1)") (class "Default")
      (node (ref "C34") (pin "1") (pinfunction "1_1") (pintype "passive"))
      (node (ref "R33") (pin "2") (pinfunction "2_2") (pintype "passive"))
      (node (ref "R41") (pin "1") (pinfunction "1_1") (pintype "passive"))
    )
    (net (code "46") (name "Net-(C37-Pad1)") (class "Default")
      (node (ref "C37") (pin "1") (pinfunction "1_1") (pintype "passive"))
      (node (ref "R36") (pin "1") (pinfunction "1_1") (pintype "passive"))
      (node (ref "R37") (pin "2") (pinfunction "2_2") (pintype "passive"))
    )
    (net (code "47") (name "Net-(C42-Pad1)") (class "Default")
      (node (ref "C42") (pin "1") (pinfunction "1_1") (pintype "passive"))
      (node (ref "D3") (pin "A") (pinfunction "A_A") (pintype "passive"))
      (node (ref "L4") (pin "2") (pinfunction "2_2") (pintype "passive"))
      (node (ref "SJ1") (pin "2") (pinfunction "2_2") (pintype "passive"))
    )
    (net (code "48") (name "Net-(D1-A1)") (class "Default")
      (node (ref "D1") (pin "1") (pinfunction "A1_1") (pintype "passive"))
      (node (ref "D2") (pin "2") (pinfunction "C2_2") (pintype "passive"))
      (node (ref "T1") (pin "4") (pinfunction "4_4") (pintype "passive"))
    )
    (net (code "49") (name "Net-(D1-C1A2)") (class "Default")
      (node (ref "D1") (pin "3") (pinfunction "C1A2_3") (pintype "passive"))
      (node (ref "T2") (pin "4") (pinfunction "4_4") (pintype "passive"))
    )
    (net (code "50") (name "Net-(D1-C2)") (class "Default")
      (node (ref "D1") (pin "2") (pinfunction "C2_2") (pintype "passive"))
      (node (ref "D2") (pin "1") (pinfunction "A1_1") (pintype "passive"))
      (node (ref "T1") (pin "3") (pinfunction "3_3") (pintype "passive"))
    )
    (net (code "51") (name "Net-(D2-C1A2)") (class "Default")
      (node (ref "D2") (pin "3") (pinfunction "C1A2_3") (pintype "passive"))
      (node (ref "T2") (pin "3") (pinfunction "3_3") (pintype "passive"))
    )
    (net (code "52") (name "Net-(J2-PadD+)") (class "Default")
      (node (ref "J2") (pin "D+") (pinfunction "D+_D+") (pintype "bidirectional"))
      (node (ref "J2") (pin "D-") (pinfunction "D-_D-") (pintype "bidirectional"))
    )
    (net (code "53") (name "Net-(J2-PadVBUS)") (class "Default")
      (node (ref "J2") (pin "VBUS") (pinfunction "VBUS_VBUS") (pintype "power_in"))
      (node (ref "L4") (pin "1") (pinfunction "1_1") (pintype "passive"))
    )
    (net (code "54") (name "Net-(L3-1)") (class "Default")
      (node (ref "L3") (pin "2") (pinfunction "1_2") (pintype "passive"))
      (node (ref "R53") (pin "2") (pinfunction "2_2") (pintype "passive"))
      (node (ref "SW1") (pin "2") (pinfunction "P_2") (pintype "passive"))
      (node (ref "U7") (pin "6") (pinfunction "VBAT_6") (pintype "bidirectional"))
      (node (ref "U7") (pin "9") (pinfunction "EN_9") (pintype "bidirectional"))
    )
    (net (code "55") (name "Net-(L3-2)") (class "Default")
      (node (ref "L3") (pin "1") (pinfunction "2_1") (pintype "passive"))
      (node (ref "U7") (pin "1") (pinfunction "SW_1") (pintype "bidirectional"))
      (node (ref "U7") (pin "2") (pinfunction "SW_2") (pintype "bidirectional"))
    )
    (net (code "56") (name "Net-(LCD1-VDD)") (class "Default")
      (node (ref "C1") (pin "1") (pinfunction "1_1") (pintype "passive"))
      (node (ref "LCD1") (pin "2") (pinfunction "VDD_2") (pintype "power_in"))
      (node (ref "Q1") (pin "3") (pinfunction "D_3") (pintype "passive"))
    )
    (net (code "57") (name "Net-(LCD1-VO)") (class "Default")
      (node (ref "LCD1") (pin "3") (pinfunction "VO_3") (pintype "input"))
      (node (ref "R1") (pin "2") (pinfunction "2_2") (pintype "passive"))
    )
    (net (code "58") (name "Net-(Q2-D)") (class "Default")
      (node (ref "C28") (pin "1") (pinfunction "1_1") (pintype "passive"))
      (node (ref "L2") (pin "2") (pinfunction "2_2") (pintype "passive"))
      (node (ref "Q2") (pin "3") (pinfunction "D_3") (pintype "passive"))
    )
    (net (code "59") (name "Net-(Q3-D)") (class "Default")
      (node (ref "B1") (pin "1") (pinfunction "1_1") (pintype "passive"))
      (node (ref "C45") (pin "1") (pinfunction "1_1") (pintype "passive"))
      (node (ref "Q3") (pin "3") (pinfunction "D_3") (pintype "passive"))
      (node (ref "R46") (pin "1") (pinfunction "1_1") (pintype "passive"))
      (node (ref "U6") (pin "5") (pinfunction "BAT_5") (pintype "passive"))
    )
    (net (code "60") (name "Net-(Q3-G)") (class "Default")
      (node (ref "Q3") (pin "1") (pinfunction "G_1") (pintype "passive"))
      (node (ref "R46") (pin "2") (pinfunction "2_2") (pintype "passive"))
      (node (ref "U6") (pin "3") (pinfunction "~{POK}_3") (pintype "output"))
    )
    (net (code "61") (name "Net-(Q3-S)") (class "Default")
      (node (ref "D3") (pin "C") (pinfunction "C_C") (pintype "passive"))
      (node (ref "P2") (pin "2") (pinfunction "2_2") (pintype "passive"))
      (node (ref "Q3") (pin "2") (pinfunction "S_2") (pintype "passive"))
      (node (ref "SW1") (pin "3") (pinfunction "S_3") (pintype "passive"))
    )
    (net (code "62") (name "Net-(R14-A)") (class "Default")
      (node (ref "C16") (pin "2") (pinfunction "2_2") (pintype "passive"))
      (node (ref "R14") (pin "1") (pinfunction "A_1") (pintype "passive"))
      (node (ref "R15") (pin "1") (pinfunction "1_1") (pintype "passive"))
      (node (ref "R16") (pin "2") (pinfunction "2_2") (pintype "passive"))
    )
    (net (code "63") (name "Net-(R14-E)") (class "Default")
      (node (ref "C8") (pin "1") (pinfunction "1_1") (pintype "passive"))
      (node (ref "R14") (pin "3") (pinfunction "E_3") (pintype "passive"))
      (node (ref "U2") (pin "1") (pinfunction "OUT_1") (pintype "output"))
    )
    (net (code "64") (name "Net-(R14-S)") (class "Default")
      (node (ref "R14") (pin "2") (pinfunction "S_2") (pintype "passive"))
      (node (ref "U2") (pin "2") (pinfunction "-IN_2") (pintype "input"))
    )
    (net (code "65") (name "Net-(R19-A)") (class "Default")
      (node (ref "C18") (pin "1") (pinfunction "1_1") (pintype "passive"))
      (node (ref "R18") (pin "1") (pinfunction "1_1") (pintype "passive"))
      (node (ref "R19") (pin "1") (pinfunction "A_1") (pintype "passive"))
    )
    (net (code "66") (name "Net-(R19-E)") (class "Default")
      (node (ref "C4") (pin "1") (pinfunction "1_1") (pintype "passive"))
      (node (ref "R19") (pin "3") (pinfunction "E_3") (pintype "passive"))
      (node (ref "TP3") (pin "1") (pinfunction "1_1") (pintype "passive"))
      (node (ref "U3") (pin "7") (pinfunction "OUT_7") (pintype "output"))
    )
    (net (code "67") (name "Net-(R19-S)") (class "Default")
      (node (ref "R19") (pin "2") (pinfunction "S_2") (pintype "passive"))
      (node (ref "U3") (pin "6") (pinfunction "-IN_6") (pintype "input"))
    )
    (net (code "68") (name "Net-(R20-A)") (class "Default")
      (node (ref "C13") (pin "1") (pinfunction "1_1") (pintype "passive"))
      (node (ref "R20") (pin "1") (pinfunction "A_1") (pintype "passive"))
      (node (ref "R21") (pin "1") (pinfunction "1_1") (pintype "passive"))
    )
    (net (code "69") (name "Net-(R20-E)") (class "Default")
      (node (ref "R13") (pin "1") (pinfunction "1_1") (pintype "passive"))
      (node (ref "R20") (pin "3") (pinfunction "E_3") (pintype "passive"))
      (node (ref "TP4") (pin "1") (pinfunction "1_1") (pintype "passive"))
      (node (ref "U3") (pin "1") (pinfunction "OUT_1") (pintype "output"))
    )
    (net (code "70") (name "Net-(R20-S)") (class "Default")
      (node (ref "R20") (pin "2") (pinfunction "S_2") (pintype "passive"))
      (node (ref "U3") (pin "2") (pinfunction "-IN_2") (pintype "input"))
    )
    (net (code "71") (name "Net-(R38-A)") (class "Default")
      (node (ref "C38") (pin "1") (pinfunction "1_1") (pintype "passive"))
      (node (ref "R37") (pin "1") (pinfunction "1_1") (pintype "passive"))
      (node (ref "R38") (pin "1") (pinfunction "A_1") (pintype "passive"))
    )
    (net (code "72") (name "Net-(R38-E)") (class "Default")
      (node (ref "C6") (pin "1") (pinfunction "1_1") (pintype "passive"))
      (node (ref "R38") (pin "3") (pinfunction "E_3") (pintype "passive"))
      (node (ref "TP7") (pin "1") (pinfunction "1_1") (pintype "passive"))
      (node (ref "U3") (pin "8") (pinfunction "OUT_8") (pintype "output"))
    )
    (net (code "73") (name "Net-(R38-S)") (class "Default")
      (node (ref "R38") (pin "2") (pinfunction "S_2") (pintype "passive"))
      (node (ref "U3") (pin "9") (pinfunction "-IN_9") (pintype "input"))
    )
    (net (code "74") (name "Net-(R39-A)") (class "Default")
      (node (ref "C33") (pin "1") (pinfunction "1_1") (pintype "passive"))
      (node (ref "R39") (pin "1") (pinfunction "A_1") (pintype "passive"))
      (node (ref "R40") (pin "1") (pinfunction "1_1") (pintype "passive"))
    )
    (net (code "75") (name "Net-(R39-E)") (class "Default")
      (node (ref "C5") (pin "1") (pinfunction "1_1") (pintype "passive"))
      (node (ref "R39") (pin "3") (pinfunction "E_3") (pintype "passive"))
      (node (ref "TP8") (pin "1") (pinfunction "1_1") (pintype "passive"))
      (node (ref "U3") (pin "14") (pinfunction "OUT_14") (pintype "output"))
    )
    (net (code "76") (name "Net-(R39-S)") (class "Default")
      (node (ref "R39") (pin "2") (pinfunction "S_2") (pintype "passive"))
      (node (ref "U3") (pin "13") (pinfunction "-IN_13") (pintype "input"))
    )
    (net (code "77") (name "Net-(U1-IND)") (class "Default")
      (node (ref "L1") (pin "2") (pinfunction "2_2") (pintype "passive"))
      (node (ref "U1") (pin "1") (pinfunction "IND_1") (pintype "bidirectional"))
    )
    (net (code "78") (name "Net-(U1-OUT+)") (class "Default")
      (node (ref "C2") (pin "1") (pinfunction "1_1") (pintype "passive"))
      (node (ref "R3") (pin "2") (pinfunction "2_2") (pintype "passive"))
      (node (ref "U1") (pin "6") (pinfunction "OUT+_6") (pintype "bidirectional"))
    )
    (net (code "79") (name "Net-(U1-OUT-)") (class "Default")
      (node (ref "C3") (pin "1") (pinfunction "1_1") (pintype "passive"))
      (node (ref "R4") (pin "2") (pinfunction "2_2") (pintype "passive"))
      (node (ref "U1") (pin "4") (pinfunction "OUT-_4") (pintype "bidirectional"))
    )
    (net (code "80") (name "Net-(U2B-+IN)") (class "Default")
      (node (ref "C23") (pin "1") (pinfunction "1_1") (pintype "passive"))
      (node (ref "R27") (pin "2") (pinfunction "2_2") (pintype "passive"))
      (node (ref "R29") (pin "1") (pinfunction "1_1") (pintype "passive"))
      (node (ref "U2") (pin "5") (pinfunction "+IN_5") (pintype "input"))
    )
    (net (code "81") (name "Net-(U2C-+IN)") (class "Default")
      (node (ref "R30") (pin "2") (pinfunction "2_2") (pintype "passive"))
      (node (ref "R31") (pin "1") (pinfunction "1_1") (pintype "passive"))
      (node (ref "U2") (pin "10") (pinfunction "+IN_10") (pintype "input"))
    )
    (net (code "82") (name "Net-(U2D-+IN)") (class "Default")
      (node (ref "U2") (pin "12") (pinfunction "+IN_12") (pintype "input"))
      (node (ref "U4") (pin "6") (pinfunction "B_6") (pintype "bidirectional"))
    )
    (net (code "83") (name "Net-(U4-A)") (class "Default")
      (node (ref "R31") (pin "2") (pinfunction "2_2") (pintype "passive"))
      (node (ref "U4") (pin "8") (pinfunction "A_8") (pintype "bidirectional"))
    )
    (net (code "84") (name "Net-(U5-PB6(XTAL1{slash}TOSC1))") (class "Default")
      (node (ref "U5") (pin "7") (pinfunction "PB6(XTAL1/TOSC1)_7") (pintype "bidirectional"))
      (node (ref "X1") (pin "1") (pinfunction "1_1") (pintype "passive"))
    )
    (net (code "85") (name "Net-(U5-PB7(XTAL2{slash}TOSC2))") (class "Default")
      (node (ref "U5") (pin "8") (pinfunction "PB7(XTAL2/TOSC2)_8") (pintype "bidirectional"))
      (node (ref "X1") (pin "3") (pinfunction "3_3") (pintype "passive"))
    )
    (net (code "86") (name "Net-(U6-DC)") (class "Default")
      (node (ref "SJ1") (pin "1") (pinfunction "1_1") (pintype "passive"))
      (node (ref "U6") (pin "4") (pinfunction "DC_4") (pintype "input"))
    )
    (net (code "87") (name "Net-(U6-USB)") (class "Default")
      (node (ref "SJ1") (pin "3") (pinfunction "3_3") (pintype "passive"))
      (node (ref "U6") (pin "1") (pinfunction "USB_1") (pintype "input"))
    )
    (net (code "88") (name "Net-(U7-FB)") (class "Default")
      (node (ref "R47") (pin "1") (pinfunction "1_1") (pintype "passive"))
      (node (ref "R51") (pin "2") (pinfunction "2_2") (pintype "passive"))
      (node (ref "U7") (pin "12") (pinfunction "FB_12") (pintype "bidirectional"))
    )
    (net (code "89") (name "Net-(U7-LBI)") (class "Default")
      (node (ref "R52") (pin "2") (pinfunction "2_2") (pintype "passive"))
      (node (ref "R53") (pin "1") (pinfunction "1_1") (pintype "passive"))
      (node (ref "U7") (pin "7") (pinfunction "LBI_7") (pintype "bidirectional"))
    )
    (net (code "90") (name "PILOT") (class "Default")
      (node (ref "R41") (pin "2") (pinfunction "2_2") (pintype "passive"))
      (node (ref "U5") (pin "14") (pinfunction "PB2(SS/OC1B)_14") (pintype "bidirectional"))
    )
    (net (code "91") (name "RBDS") (class "Default")
      (node (ref "C9") (pin "2") (pinfunction "2_2") (pintype "passive"))
      (node (ref "R12") (pin "1") (pinfunction "1_1") (pintype "passive"))
      (node (ref "R17") (pin "2") (pinfunction "2_2") (pintype "passive"))
      (node (ref "R6") (pin "2") (pinfunction "2_2") (pintype "passive"))
      (node (ref "TP1") (pin "1") (pinfunction "1_1") (pintype "passive"))
    )
    (net (code "92") (name "RXD") (class "Default")
      (node (ref "P1") (pin "2") (pinfunction "2_2") (pintype "passive"))
      (node (ref "U5") (pin "30") (pinfunction "PD0(RXD)_30") (pintype "bidirectional"))
    )
    (net (code "93") (name "SCK") (class "Default")
      (node (ref "R44") (pin "1") (pinfunction "1_1") (pintype "passive"))
      (node (ref "U4") (pin "3") (pinfunction "SCK_3") (pintype "bidirectional"))
    )
    (net (code "94") (name "SIGNAL") (class "Default")
      (node (ref "C15") (pin "1") (pinfunction "1_1") (pintype "passive"))
      (node (ref "C8") (pin "2") (pinfunction "2_2") (pintype "passive"))
      (node (ref "R7") (pin "2") (pinfunction "2_2") (pintype "passive"))
      (node (ref "R8") (pin "1") (pinfunction "1_1") (pintype "passive"))
      (node (ref "TP2") (pin "1") (pinfunction "1_1") (pintype "passive"))
      (node (ref "U1") (pin "3") (pinfunction "TUNE_3") (pintype "bidirectional"))
    )
    (net (code "95") (name "TONE") (class "Default")
      (node (ref "R35") (pin "2") (pinfunction "2_2") (pintype "passive"))
      (node (ref "U5") (pin "1") (pinfunction "PD3(INT1)_1") (pintype "bidirectional"))
    )
    (net (code "96") (name "VCC") (class "Default")
      (node (ref "C10") (pin "1") (pinfunction "1_1") (pintype "passive"))
      (node (ref "C11") (pin "1") (pinfunction "1_1") (pintype "passive"))
      (node (ref "C24") (pin "1") (pinfunction "1_1") (pintype "passive"))
      (node (ref "C25") (pin "1") (pinfunction "1_1") (pintype "passive"))
      (node (ref "C26") (pin "1") (pinfunction "1_1") (pintype "passive"))
      (node (ref "C27") (pin "1") (pinfunction "1_1") (pintype "passive"))
      (node (ref "C35") (pin "1") (pinfunction "1_1") (pintype "passive"))
      (node (ref "C36") (pin "1") (pinfunction "1_1") (pintype "passive"))
      (node (ref "L2") (pin "1") (pinfunction "1_1") (pintype "passive"))
      (node (ref "R16") (pin "1") (pinfunction "1_1") (pintype "passive"))
      (node (ref "R27") (pin "1") (pinfunction "1_1") (pintype "passive"))
      (node (ref "R3") (pin "1") (pinfunction "1_1") (pintype "passive"))
      (node (ref "R4") (pin "1") (pinfunction "1_1") (pintype "passive"))
      (node (ref "R6") (pin "1") (pinfunction "1_1") (pintype "passive"))
      (node (ref "U1") (pin "5") (pinfunction "VCC_5") (pintype "bidirectional"))
      (node (ref "U2") (pin "4") (pinfunction "V+_4") (pintype "power_in"))
      (node (ref "U3") (pin "4") (pinfunction "V+_4") (pintype "power_in"))
      (node (ref "U4") (pin "1") (pinfunction "VDD_1") (pintype "bidirectional"))
    )
    (net (code "97") (name "unconnected-(J2-PadID)") (class "Default")
      (node (ref "J2") (pin "ID") (pinfunction "ID_ID") (pintype "bidirectional"))
    )
    (net (code "98") (name "unconnected-(LCD1-A-Pad15)") (class "Default")
      (node (ref "LCD1") (pin "15") (pinfunction "A_15") (pintype "input"))
    )
    (net (code "99") (name "unconnected-(LCD1-DB0-Pad7)") (class "Default")
      (node (ref "LCD1") (pin "7") (pinfunction "DB0_7") (pintype "bidirectional"))
    )
    (net (code "100") (name "unconnected-(LCD1-DB1-Pad8)") (class "Default")
      (node (ref "LCD1") (pin "8") (pinfunction "DB1_8") (pintype "bidirectional"))
    )
    (net (code "101") (name "unconnected-(LCD1-DB2-Pad9)") (class "Default")
      (node (ref "LCD1") (pin "9") (pinfunction "DB2_9") (pintype "bidirectional"))
    )
    (net (code "102") (name "unconnected-(LCD1-DB3-Pad10)") (class "Default")
      (node (ref "LCD1") (pin "10") (pinfunction "DB3_10") (pintype "bidirectional"))
    )
    (net (code "103") (name "unconnected-(LCD1-K-Pad16)") (class "Default")
      (node (ref "LCD1") (pin "16") (pinfunction "K_16") (pintype "input"))
    )
    (net (code "104") (name "unconnected-(SW1-O-Pad1)") (class "Default")
      (node (ref "SW1") (pin "1") (pinfunction "O_1") (pintype "passive"))
    )
    (net (code "105") (name "unconnected-(U5-ADC6-Pad19)") (class "Default")
      (node (ref "U5") (pin "19") (pinfunction "ADC6_19") (pintype "bidirectional"))
    )
    (net (code "106") (name "unconnected-(U5-ADC7-Pad22)") (class "Default")
      (node (ref "U5") (pin "22") (pinfunction "ADC7_22") (pintype "bidirectional"))
    )
    (net (code "107") (name "unconnected-(U5-PB0(ICP)-Pad12)") (class "Default")
      (node (ref "U5") (pin "12") (pinfunction "PB0(ICP)_12") (pintype "bidirectional"))
    )
    (net (code "108") (name "unconnected-(U5-PD7(AIN1)-Pad11)") (class "Default")
      (node (ref "U5") (pin "11") (pinfunction "PD7(AIN1)_11") (pintype "bidirectional"))
    )
  )
)
